# RX-Super-Regenerative-Airband-1Transisto.net
KiCad netlist of a schematic drawn in EAGLE
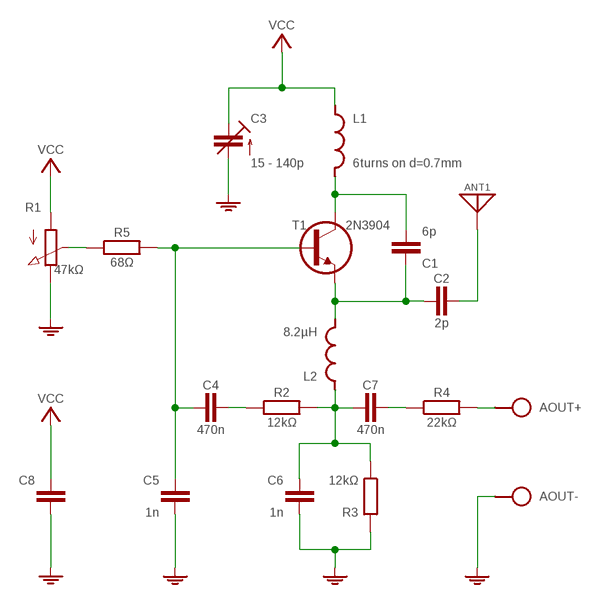
[diagram p0: schematic, sheet 1]

(export (version "E")
  (design (tool "Eeschema 10.0.6"))
  (components
    (comp (ref "ANT1")
      (value "ANT")
      (footprint "eagle-import:SPAD")
      (libsource (lib "eagle-import") (part "ANT"))
    )
    (comp (ref "AOUT+")
      (value "SPAD")
      (footprint "eagle-import:SPAD")
      (libsource (lib "eagle-import") (part "SPAD"))
    )
    (comp (ref "AOUT-")
      (value "SPAD")
      (footprint "eagle-import:SPAD")
      (libsource (lib "eagle-import") (part "SPAD"))
    )
    (comp (ref "C1")
      (value "6p")
      (footprint "eagle-import:C050-020X036")
      (libsource (lib "eagle-import") (part "C050-020X036"))
    )
    (comp (ref "C2")
      (value "2p")
      (footprint "eagle-import:C025-015X024")
      (libsource (lib "eagle-import") (part "C025-015X024"))
    )
    (comp (ref "C3")
      (value "15 - 140p")
      (footprint "eagle-import:TRIM-2222-808")
      (libsource (lib "eagle-import") (part "C-TR-PH201272222-808-2PINB"))
    )
    (comp (ref "C4")
      (value "470n")
      (footprint "eagle-import:C050-020X036")
      (libsource (lib "eagle-import") (part "C050-020X036"))
    )
    (comp (ref "C5")
      (value "1n")
      (footprint "eagle-import:C025-020X036")
      (libsource (lib "eagle-import") (part "C025-020X036"))
    )
    (comp (ref "C6")
      (value "1n")
      (footprint "eagle-import:C050-020X036")
      (libsource (lib "eagle-import") (part "C050-020X036"))
    )
    (comp (ref "C7")
      (value "470n")
      (footprint "eagle-import:C050-020X036")
      (libsource (lib "eagle-import") (part "C050-020X036"))
    )
    (comp (ref "C8")
      (value "C050-025X075")
      (footprint "eagle-import:C050-025X075")
      (libsource (lib "eagle-import") (part "C050-025X075"))
    )
    (comp (ref "L1")
      (value "6turns on d=0.7mm")
      (footprint "eagle-import:L-04_7V-X")
      (libsource (lib "eagle-import") (part "L-SHORTL-04/7V-X"))
    )
    (comp (ref "L2")
      (value "8.2µH")
      (footprint "eagle-import:L-04-5_6V")
      (libsource (lib "eagle-import") (part "L-SHORT04-5/5V"))
    )
    (comp (ref "R1")
      (value "47kΩ")
      (footprint "eagle-import:POT")
      (libsource (lib "eagle-import") (part "POT"))
    )
    (comp (ref "R2")
      (value "12kΩ")
      (footprint "eagle-import:0202_7")
      (libsource (lib "eagle-import") (part "R-H0202/7"))
    )
    (comp (ref "R3")
      (value "12kΩ")
      (footprint "eagle-import:0202_7")
      (libsource (lib "eagle-import") (part "R0202/7"))
    )
    (comp (ref "R4")
      (value "22kΩ")
      (footprint "eagle-import:0202_7")
      (libsource (lib "eagle-import") (part "R-H0202/7"))
    )
    (comp (ref "R5")
      (value "68Ω")
      (footprint "eagle-import:0202_7")
      (libsource (lib "eagle-import") (part "R-H0202/7"))
    )
    (comp (ref "S1")
      (value "VCC_GNDPWR-L")
      (footprint "eagle-import:PWR-L")
      (libsource (lib "eagle-import") (part "VCC_GNDPWR-L"))
    )
    (comp (ref "T1")
      (value "2N3904")
      (footprint "eagle-import:TO92")
      (libsource (lib "eagle-import") (part "2N3904"))
    )
  )
  (nets
    (net (code "1") (name "GND") (class "Default")
      (node (ref "AOUT-") (pin "1") (pinfunction "P$1_1") (pintype "bidirectional"))
      (node (ref "C3") (pin "2") (pinfunction "A_2") (pintype "passive"))
      (node (ref "C5") (pin "2") (pinfunction "2_2") (pintype "passive"))
      (node (ref "C6") (pin "2") (pinfunction "2_2") (pintype "passive"))
      (node (ref "C8") (pin "2") (pinfunction "2_2") (pintype "passive"))
      (node (ref "R1") (pin "3") (pinfunction "E_3") (pintype "passive"))
      (node (ref "R3") (pin "2") (pinfunction "2_2") (pintype "passive"))
      (node (ref "S1") (pin "1") (pinfunction "GND_1") (pintype "power_in"))
    )
    (net (code "2") (name "Net-(ANT1-Pad1)") (class "Default")
      (node (ref "ANT1") (pin "1") (pinfunction "1_1") (pintype "output"))
      (node (ref "C2") (pin "1") (pinfunction "1_1") (pintype "passive"))
    )
    (net (code "3") (name "Net-(AOUT+-P$1)") (class "Default")
      (node (ref "AOUT+") (pin "1") (pinfunction "P$1_1") (pintype "bidirectional"))
      (node (ref "R4") (pin "2") (pinfunction "2_2") (pintype "passive"))
    )
    (net (code "4") (name "Net-(C4-Pad1)") (class "Default")
      (node (ref "C4") (pin "1") (pinfunction "1_1") (pintype "passive"))
      (node (ref "R2") (pin "1") (pinfunction "1_1") (pintype "passive"))
    )
    (net (code "5") (name "Net-(C6-Pad1)") (class "Default")
      (node (ref "C6") (pin "1") (pinfunction "1_1") (pintype "passive"))
      (node (ref "C7") (pin "2") (pinfunction "2_2") (pintype "passive"))
      (node (ref "L2") (pin "2") (pinfunction "2_2") (pintype "passive"))
      (node (ref "R2") (pin "2") (pinfunction "2_2") (pintype "passive"))
      (node (ref "R3") (pin "1") (pinfunction "1_1") (pintype "passive"))
    )
    (net (code "6") (name "Net-(C7-Pad1)") (class "Default")
      (node (ref "C7") (pin "1") (pinfunction "1_1") (pintype "passive"))
      (node (ref "R4") (pin "1") (pinfunction "1_1") (pintype "passive"))
    )
    (net (code "7") (name "Net-(R1-S)") (class "Default")
      (node (ref "R1") (pin "2") (pinfunction "S_2") (pintype "passive"))
      (node (ref "R5") (pin "1") (pinfunction "1_1") (pintype "passive"))
    )
    (net (code "8") (name "Net-(T1-B)") (class "Default")
      (node (ref "C4") (pin "2") (pinfunction "2_2") (pintype "passive"))
      (node (ref "C5") (pin "1") (pinfunction "1_1") (pintype "passive"))
      (node (ref "R5") (pin "2") (pinfunction "2_2") (pintype "passive"))
      (node (ref "T1") (pin "2") (pinfunction "B_2") (pintype "passive"))
    )
    (net (code "9") (name "Net-(T1-C)") (class "Default")
      (node (ref "C1") (pin "2") (pinfunction "2_2") (pintype "passive"))
      (node (ref "L1") (pin "1") (pinfunction "1_1") (pintype "passive"))
      (node (ref "T1") (pin "3") (pinfunction "C_3") (pintype "passive"))
    )
    (net (code "10") (name "Net-(T1-E)") (class "Default")
      (node (ref "C1") (pin "1") (pinfunction "1_1") (pintype "passive"))
      (node (ref "C2") (pin "2") (pinfunction "2_2") (pintype "passive"))
      (node (ref "L2") (pin "1") (pinfunction "1_1") (pintype "passive"))
      (node (ref "T1") (pin "1") (pinfunction "E_1") (pintype "passive"))
    )
    (net (code "11") (name "VCC") (class "Default")
      (node (ref "C3") (pin "3") (pinfunction "E_3") (pintype "passive"))
      (node (ref "C8") (pin "1") (pinfunction "1_1") (pintype "passive"))
      (node (ref "L1") (pin "2") (pinfunction "2_2") (pintype "passive"))
      (node (ref "R1") (pin "1") (pinfunction "A_1") (pintype "passive"))
      (node (ref "S1") (pin "2") (pinfunction "VCC_2") (pintype "power_in"))
    )
  )
)
